# NES_IO_FR.net
KiCad netlist of a schematic drawn in EAGLE
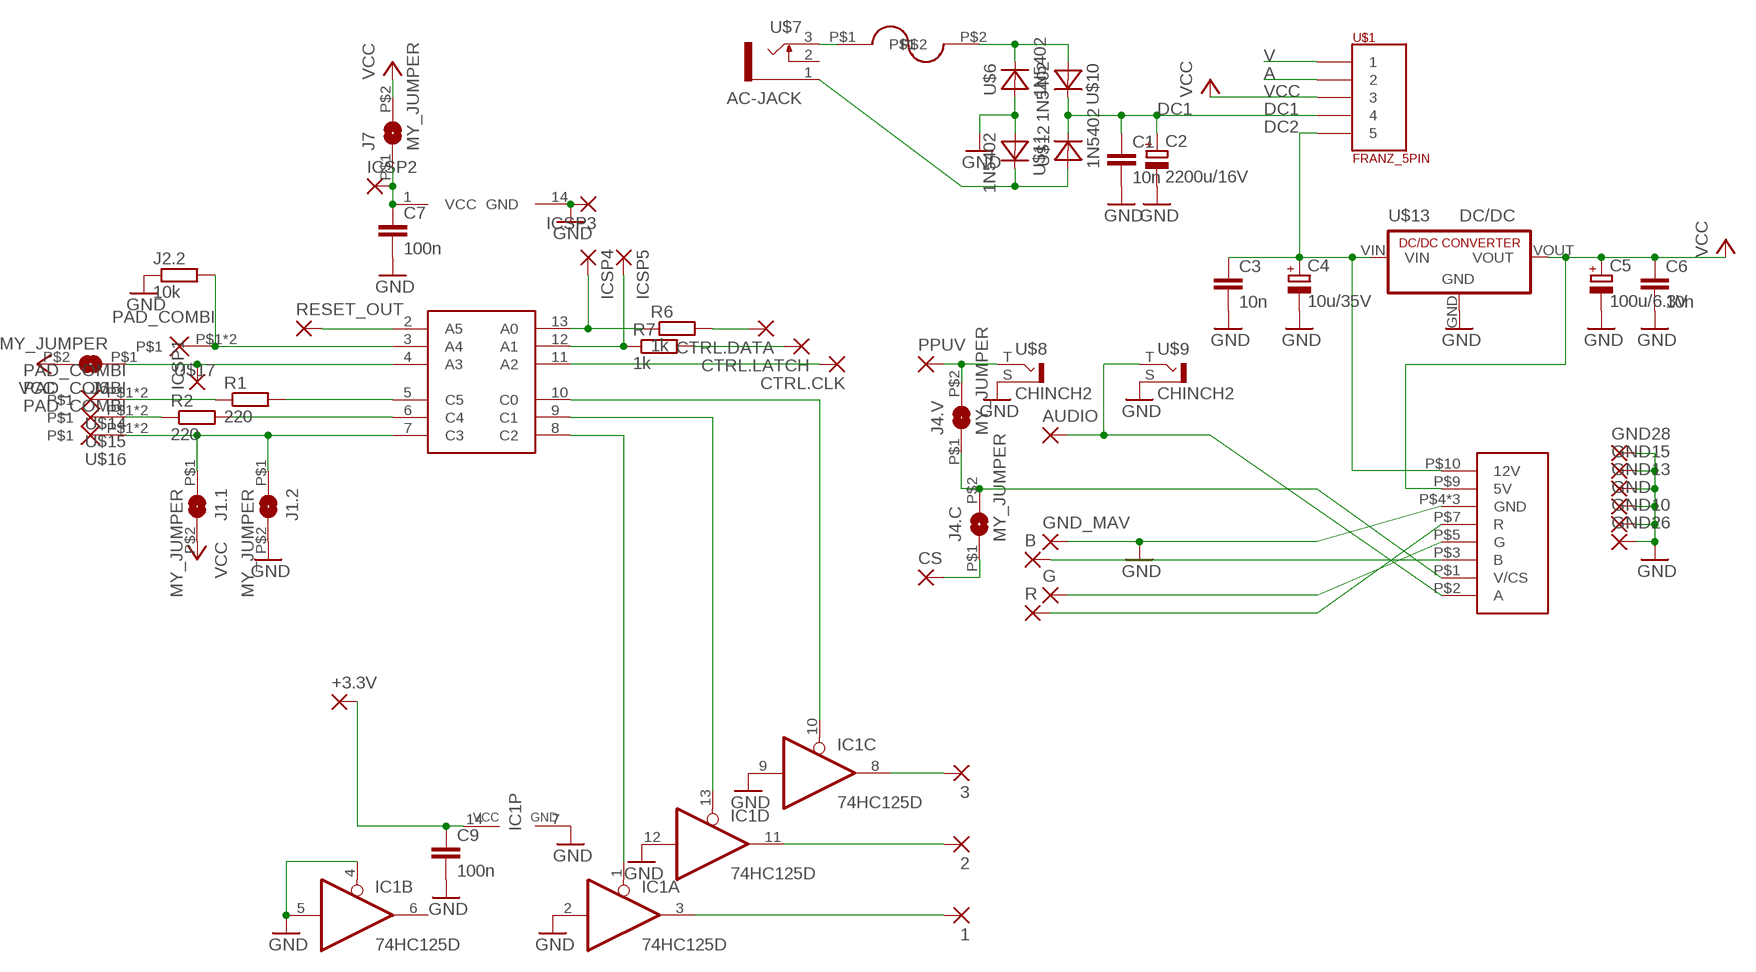
[diagram p0: schematic, sheet 1]

(export (version "E")
  (design (tool "Eeschema 10.0.6"))
  (components
    (comp (ref "+3.3V")
      (value "SMD2")
      (footprint "eagle-import:SMD1,27-2,54")
      (libsource (lib "eagle-import") (part "SMD2"))
    )
    (comp (ref "1")
      (value "SMD2")
      (footprint "eagle-import:SMD1,27-2,54")
      (libsource (lib "eagle-import") (part "SMD2"))
    )
    (comp (ref "2")
      (value "SMD2")
      (footprint "eagle-import:SMD1,27-2,54")
      (libsource (lib "eagle-import") (part "SMD2"))
    )
    (comp (ref "3")
      (value "SMD2")
      (footprint "eagle-import:SMD1,27-2,54")
      (libsource (lib "eagle-import") (part "SMD2"))
    )
    (comp (ref "AUDIO")
      (value "SMD2")
      (footprint "eagle-import:SMD1,27-2,54")
      (libsource (lib "eagle-import") (part "SMD2"))
    )
    (comp (ref "B")
      (value "SMD2")
      (footprint "eagle-import:SMD1,27-2,54")
      (libsource (lib "eagle-import") (part "SMD2"))
    )
    (comp (ref "C1")
      (value "10n")
      (footprint "eagle-import:Z0805")
      (libsource (lib "eagle-import") (part "C0805"))
    )
    (comp (ref "C2")
      (value "2200u/16V")
      (footprint "eagle-import:E5-13")
      (libsource (lib "eagle-import") (part "resistor_CPOL-EUE5-13"))
    )
    (comp (ref "C3")
      (value "10n")
      (footprint "eagle-import:Z0805")
      (libsource (lib "eagle-import") (part "C0805"))
    )
    (comp (ref "C4")
      (value "10u/35V")
      (footprint "eagle-import:PANASONIC_B")
      (libsource (lib "eagle-import") (part "CPOL-EUB"))
    )
    (comp (ref "C5")
      (value "100u/6.3V")
      (footprint "eagle-import:PANASONIC_D")
      (libsource (lib "eagle-import") (part "CPOL-EUD"))
    )
    (comp (ref "C6")
      (value "10n")
      (footprint "eagle-import:Z0805")
      (libsource (lib "eagle-import") (part "C0805"))
    )
    (comp (ref "C7")
      (value "100n")
      (footprint "eagle-import:Z0805")
      (libsource (lib "eagle-import") (part "C0805"))
    )
    (comp (ref "C9")
      (value "100n")
      (footprint "eagle-import:Z0805")
      (libsource (lib "eagle-import") (part "C0805"))
    )
    (comp (ref "CS")
      (value "SMD2")
      (footprint "eagle-import:SMD1,27-2,54")
      (libsource (lib "eagle-import") (part "SMD2"))
    )
    (comp (ref "CTRL.CLK")
      (value "SMD2")
      (footprint "eagle-import:SMD1,27-2,54")
      (libsource (lib "eagle-import") (part "SMD2"))
    )
    (comp (ref "CTRL.DATA")
      (value "SMD2")
      (footprint "eagle-import:SMD1,27-2,54")
      (libsource (lib "eagle-import") (part "SMD2"))
    )
    (comp (ref "CTRL.LATCH")
      (value "SMD2")
      (footprint "eagle-import:SMD1,27-2,54")
      (libsource (lib "eagle-import") (part "SMD2"))
    )
    (comp (ref "G")
      (value "SMD2")
      (footprint "eagle-import:SMD1,27-2,54")
      (libsource (lib "eagle-import") (part "SMD2"))
    )
    (comp (ref "GND")
      (value "SMD5")
      (footprint "eagle-import:SMD2,54-5,08")
      (libsource (lib "eagle-import") (part "SMD5"))
    )
    (comp (ref "GND10")
      (value "SMD5")
      (footprint "eagle-import:SMD2,54-5,08")
      (libsource (lib "eagle-import") (part "SMD5"))
    )
    (comp (ref "GND13")
      (value "SMD5")
      (footprint "eagle-import:SMD2,54-5,08")
      (libsource (lib "eagle-import") (part "SMD5"))
    )
    (comp (ref "GND15")
      (value "SMD5")
      (footprint "eagle-import:SMD2,54-5,08")
      (libsource (lib "eagle-import") (part "SMD5"))
    )
    (comp (ref "GND26")
      (value "SMD5")
      (footprint "eagle-import:SMD2,54-5,08")
      (libsource (lib "eagle-import") (part "SMD5"))
    )
    (comp (ref "GND28")
      (value "SMD5")
      (footprint "eagle-import:SMD2,54-5,08")
      (libsource (lib "eagle-import") (part "SMD5"))
    )
    (comp (ref "GND_MAV")
      (value "SMD2")
      (footprint "eagle-import:SMD1,27-2,54")
      (libsource (lib "eagle-import") (part "SMD2"))
    )
    (comp (ref "IC1")
      (value "74HC125D")
      (footprint "eagle-import:SO14")
      (libsource (lib "eagle-import") (part "74125DHC"))
    )
    (comp (ref "ICSP1")
      (value "1,6/0,8")
      (footprint "eagle-import:1,6_0,8")
      (libsource (lib "eagle-import") (part "1,6/0,8"))
    )
    (comp (ref "ICSP2")
      (value "1,6/0,8")
      (footprint "eagle-import:1,6_0,8")
      (libsource (lib "eagle-import") (part "1,6/0,8"))
    )
    (comp (ref "ICSP3")
      (value "1,6/0,8")
      (footprint "eagle-import:1,6_0,8")
      (libsource (lib "eagle-import") (part "1,6/0,8"))
    )
    (comp (ref "ICSP4")
      (value "1,6/0,8")
      (footprint "eagle-import:1,6_0,8")
      (libsource (lib "eagle-import") (part "1,6/0,8"))
    )
    (comp (ref "ICSP5")
      (value "1,6/0,8")
      (footprint "eagle-import:1,6_0,8")
      (libsource (lib "eagle-import") (part "1,6/0,8"))
    )
    (comp (ref "J1.1")
      (value "MY_JUMPER")
      (footprint "eagle-import:MYJUMP")
      (libsource (lib "eagle-import") (part "MY_JUMPER"))
    )
    (comp (ref "J1.2")
      (value "MY_JUMPER")
      (footprint "eagle-import:MYJUMP")
      (libsource (lib "eagle-import") (part "MY_JUMPER"))
    )
    (comp (ref "J2.2")
      (value "10k")
      (footprint "eagle-import:Z0805")
      (libsource (lib "eagle-import") (part "R0805"))
    )
    (comp (ref "J4.C")
      (value "MY_JUMPER")
      (footprint "eagle-import:MYJUMP")
      (libsource (lib "eagle-import") (part "MY_JUMPER"))
    )
    (comp (ref "J4.V")
      (value "MY_JUMPER")
      (footprint "eagle-import:MYJUMP")
      (libsource (lib "eagle-import") (part "MY_JUMPER"))
    )
    (comp (ref "J6")
      (value "MY_JUMPER")
      (footprint "eagle-import:MYJUMP")
      (libsource (lib "eagle-import") (part "MY_JUMPER"))
    )
    (comp (ref "J7")
      (value "MY_JUMPER")
      (footprint "eagle-import:MYJUMP")
      (libsource (lib "eagle-import") (part "MY_JUMPER"))
    )
    (comp (ref "PPUV")
      (value "SMD2")
      (footprint "eagle-import:SMD1,27-2,54")
      (libsource (lib "eagle-import") (part "SMD2"))
    )
    (comp (ref "R")
      (value "SMD2")
      (footprint "eagle-import:SMD1,27-2,54")
      (libsource (lib "eagle-import") (part "SMD2"))
    )
    (comp (ref "R1")
      (value "220")
      (footprint "eagle-import:Z0805")
      (libsource (lib "eagle-import") (part "R0805"))
    )
    (comp (ref "R2")
      (value "220")
      (footprint "eagle-import:Z0805")
      (libsource (lib "eagle-import") (part "R0805"))
    )
    (comp (ref "R6")
      (value "1k")
      (footprint "eagle-import:Z0805")
      (libsource (lib "eagle-import") (part "R0805"))
    )
    (comp (ref "R7")
      (value "1k")
      (footprint "eagle-import:Z0805")
      (libsource (lib "eagle-import") (part "R0805"))
    )
    (comp (ref "RESET_OUT")
      (value "SMD2")
      (footprint "eagle-import:SMD1,27-2,54")
      (libsource (lib "eagle-import") (part "SMD2"))
    )
    (comp (ref "U$1")
      (value "FRANZ_5PIN")
      (footprint "eagle-import:5X2.22RM4")
      (libsource (lib "eagle-import") (part "FRANZ_5PIN"))
    )
    (comp (ref "U$2")
      (value "FUSEHOLDER")
      (footprint "eagle-import:FUSEHOLDER")
      (libsource (lib "eagle-import") (part "FUSEHOLDER"))
    )
    (comp (ref "U$5")
      (value "PIC16F630_SIMPLE")
      (footprint "eagle-import:PIC16F630")
      (libsource (lib "eagle-import") (part "PIC16F630_SIMPLE"))
    )
    (comp (ref "U$6")
      (value "1N5402")
      (footprint "eagle-import:DO201")
      (libsource (lib "eagle-import") (part "1N5402"))
    )
    (comp (ref "U$7")
      (value "AC-JACK")
      (footprint "eagle-import:AC-JACK")
      (libsource (lib "eagle-import") (part "AC-JACK"))
    )
    (comp (ref "U$8")
      (value "CHINCH2")
      (footprint "eagle-import:CHINCH")
      (libsource (lib "eagle-import") (part "CHINCH2"))
    )
    (comp (ref "U$9")
      (value "CHINCH2")
      (footprint "eagle-import:CHINCH")
      (libsource (lib "eagle-import") (part "CHINCH2"))
    )
    (comp (ref "U$10")
      (value "1N5402")
      (footprint "eagle-import:DO201")
      (libsource (lib "eagle-import") (part "1N5402"))
    )
    (comp (ref "U$11")
      (value "1N5402")
      (footprint "eagle-import:DO201")
      (libsource (lib "eagle-import") (part "1N5402"))
    )
    (comp (ref "U$12")
      (value "1N5402")
      (footprint "eagle-import:DO201")
      (libsource (lib "eagle-import") (part "1N5402"))
    )
    (comp (ref "U$13")
      (value "DC/DC")
      (footprint "eagle-import:RECOM")
      (libsource (lib "eagle-import") (part "DC/DC"))
    )
    (comp (ref "U$14")
      (value "PAD_COMBI")
      (footprint "eagle-import:PAD_COMBI")
      (libsource (lib "eagle-import") (part "PAD_COMBI"))
    )
    (comp (ref "U$15")
      (value "PAD_COMBI")
      (footprint "eagle-import:PAD_COMBI")
      (libsource (lib "eagle-import") (part "PAD_COMBI"))
    )
    (comp (ref "U$16")
      (value "PAD_COMBI")
      (footprint "eagle-import:PAD_COMBI")
      (libsource (lib "eagle-import") (part "PAD_COMBI"))
    )
    (comp (ref "U$17")
      (value "PAD_COMBI")
      (footprint "eagle-import:PAD_COMBI")
      (libsource (lib "eagle-import") (part "PAD_COMBI"))
    )
    (comp (ref "U$18")
      (value "NESFR_JACK")
      (footprint "eagle-import:NESFR_JACK")
      (libsource (lib "eagle-import") (part "NESFR_JACK"))
    )
  )
  (nets
    (net (code "1") (name "/A") (class "Default")
      (node (ref "U$1") (pin "P$2") (pinfunction "2_P$2") (pintype "bidirectional"))
    )
    (net (code "2") (name "/DC1") (class "Default")
      (node (ref "C1") (pin "1") (pinfunction "1_1") (pintype "passive"))
      (node (ref "C2") (pin "+") (pinfunction "+_+") (pintype "passive"))
      (node (ref "U$1") (pin "P$4") (pinfunction "4_P$4") (pintype "bidirectional"))
      (node (ref "U$10") (pin "C") (pinfunction "C_C") (pintype "passive"))
      (node (ref "U$12") (pin "C") (pinfunction "C_C") (pintype "passive"))
    )
    (net (code "3") (name "/DC2") (class "Default")
      (node (ref "C3") (pin "1") (pinfunction "1_1") (pintype "passive"))
      (node (ref "C4") (pin "+") (pinfunction "+_+") (pintype "passive"))
      (node (ref "U$1") (pin "P$5") (pinfunction "5_P$5") (pintype "bidirectional"))
      (node (ref "U$13") (pin "VIN") (pinfunction "VIN_VIN") (pintype "passive"))
      (node (ref "U$18") (pin "P$10") (pinfunction "12V_P$10") (pintype "bidirectional"))
    )
    (net (code "4") (name "/V") (class "Default")
      (node (ref "U$1") (pin "P$1") (pinfunction "1_P$1") (pintype "bidirectional"))
    )
    (net (code "5") (name "GND") (class "Default")
      (node (ref "C1") (pin "2") (pinfunction "2_2") (pintype "passive"))
      (node (ref "C2") (pin "-") (pinfunction "-_-") (pintype "passive"))
      (node (ref "C3") (pin "2") (pinfunction "2_2") (pintype "passive"))
      (node (ref "C4") (pin "-") (pinfunction "-_-") (pintype "passive"))
      (node (ref "C5") (pin "-") (pinfunction "-_-") (pintype "passive"))
      (node (ref "C6") (pin "2") (pinfunction "2_2") (pintype "passive"))
      (node (ref "C7") (pin "2") (pinfunction "2_2") (pintype "passive"))
      (node (ref "C9") (pin "2") (pinfunction "2_2") (pintype "passive"))
      (node (ref "GND") (pin "1") (pinfunction "P_1") (pintype "passive"))
      (node (ref "GND10") (pin "1") (pinfunction "P_1") (pintype "passive"))
      (node (ref "GND13") (pin "1") (pinfunction "P_1") (pintype "passive"))
      (node (ref "GND15") (pin "1") (pinfunction "P_1") (pintype "passive"))
      (node (ref "GND26") (pin "1") (pinfunction "P_1") (pintype "passive"))
      (node (ref "GND28") (pin "1") (pinfunction "P_1") (pintype "passive"))
      (node (ref "GND_MAV") (pin "1") (pinfunction "P_1") (pintype "passive"))
      (node (ref "IC1") (pin "12") (pinfunction "I_12") (pintype "input"))
      (node (ref "IC1") (pin "2") (pinfunction "I_2") (pintype "input"))
      (node (ref "IC1") (pin "4") (pinfunction "OE_4") (pintype "input"))
      (node (ref "IC1") (pin "5") (pinfunction "I_5") (pintype "input"))
      (node (ref "IC1") (pin "7") (pinfunction "GND_7") (pintype "power_in"))
      (node (ref "IC1") (pin "9") (pinfunction "I_9") (pintype "input"))
      (node (ref "ICSP3") (pin "1") (pinfunction "P_1") (pintype "passive"))
      (node (ref "J1.2") (pin "P$2") (pinfunction "2_P$2") (pintype "passive"))
      (node (ref "J2.2") (pin "1") (pinfunction "1_1") (pintype "passive"))
      (node (ref "U$11") (pin "A") (pinfunction "A_A") (pintype "passive"))
      (node (ref "U$13") (pin "GND") (pinfunction "GND_GND") (pintype "passive"))
      (node (ref "U$18") (pin "P$4") (pinfunction "GND_P$4") (pintype "bidirectional"))
      (node (ref "U$18") (pin "P$6") (pinfunction "GND_P$6") (pintype "bidirectional"))
      (node (ref "U$18") (pin "P$8") (pinfunction "GND_P$8") (pintype "bidirectional"))
      (node (ref "U$5") (pin "14") (pinfunction "GND_14") (pintype "bidirectional"))
      (node (ref "U$6") (pin "A") (pinfunction "A_A") (pintype "passive"))
      (node (ref "U$8") (pin "S") (pinfunction "S_S") (pintype "passive"))
      (node (ref "U$9") (pin "S") (pinfunction "S_S") (pintype "passive"))
    )
    (net (code "6") (name "Net-(+3.3V-P)") (class "Default")
      (node (ref "+3.3V") (pin "1") (pinfunction "P_1") (pintype "passive"))
      (node (ref "C9") (pin "1") (pinfunction "1_1") (pintype "passive"))
      (node (ref "IC1") (pin "14") (pinfunction "VCC_14") (pintype "power_in"))
    )
    (net (code "7") (name "Net-(1-P)") (class "Default")
      (node (ref "1") (pin "1") (pinfunction "P_1") (pintype "passive"))
      (node (ref "IC1") (pin "3") (pinfunction "O_3") (pintype "tri_state"))
    )
    (net (code "8") (name "Net-(2-P)") (class "Default")
      (node (ref "2") (pin "1") (pinfunction "P_1") (pintype "passive"))
      (node (ref "IC1") (pin "11") (pinfunction "O_11") (pintype "tri_state"))
    )
    (net (code "9") (name "Net-(3-P)") (class "Default")
      (node (ref "3") (pin "1") (pinfunction "P_1") (pintype "passive"))
      (node (ref "IC1") (pin "8") (pinfunction "O_8") (pintype "tri_state"))
    )
    (net (code "10") (name "Net-(AUDIO-P)") (class "Default")
      (node (ref "AUDIO") (pin "1") (pinfunction "P_1") (pintype "passive"))
      (node (ref "U$18") (pin "P$2") (pinfunction "A_P$2") (pintype "bidirectional"))
      (node (ref "U$9") (pin "T") (pinfunction "T_T") (pintype "passive"))
    )
    (net (code "11") (name "Net-(B-P)") (class "Default")
      (node (ref "B") (pin "1") (pinfunction "P_1") (pintype "passive"))
      (node (ref "U$18") (pin "P$3") (pinfunction "B_P$3") (pintype "bidirectional"))
    )
    (net (code "12") (name "Net-(CS-P)") (class "Default")
      (node (ref "CS") (pin "1") (pinfunction "P_1") (pintype "passive"))
      (node (ref "J4.C") (pin "P$1") (pinfunction "1_P$1") (pintype "passive"))
    )
    (net (code "13") (name "Net-(CTRL.CLK-P)") (class "Default")
      (node (ref "CTRL.CLK") (pin "1") (pinfunction "P_1") (pintype "passive"))
      (node (ref "U$5") (pin "11") (pinfunction "A2_11") (pintype "bidirectional"))
    )
    (net (code "14") (name "Net-(CTRL.DATA-P)") (class "Default")
      (node (ref "CTRL.DATA") (pin "1") (pinfunction "P_1") (pintype "passive"))
      (node (ref "R6") (pin "2") (pinfunction "2_2") (pintype "passive"))
    )
    (net (code "15") (name "Net-(CTRL.LATCH-P)") (class "Default")
      (node (ref "CTRL.LATCH") (pin "1") (pinfunction "P_1") (pintype "passive"))
      (node (ref "R7") (pin "2") (pinfunction "2_2") (pintype "passive"))
    )
    (net (code "16") (name "Net-(G-P)") (class "Default")
      (node (ref "G") (pin "1") (pinfunction "P_1") (pintype "passive"))
      (node (ref "U$18") (pin "P$5") (pinfunction "G_P$5") (pintype "bidirectional"))
    )
    (net (code "17") (name "Net-(IC1A-OE)") (class "Default")
      (node (ref "IC1") (pin "1") (pinfunction "OE_1") (pintype "input"))
      (node (ref "U$5") (pin "8") (pinfunction "C2_8") (pintype "bidirectional"))
    )
    (net (code "18") (name "Net-(IC1C-OE)") (class "Default")
      (node (ref "IC1") (pin "10") (pinfunction "OE_10") (pintype "input"))
      (node (ref "U$5") (pin "10") (pinfunction "C0_10") (pintype "bidirectional"))
    )
    (net (code "19") (name "Net-(IC1D-OE)") (class "Default")
      (node (ref "IC1") (pin "13") (pinfunction "OE_13") (pintype "input"))
      (node (ref "U$5") (pin "9") (pinfunction "C1_9") (pintype "bidirectional"))
    )
    (net (code "20") (name "Net-(ICSP1-P)") (class "Default")
      (node (ref "ICSP1") (pin "1") (pinfunction "P_1") (pintype "passive"))
      (node (ref "J6") (pin "P$1") (pinfunction "1_P$1") (pintype "passive"))
      (node (ref "U$5") (pin "4") (pinfunction "A3_4") (pintype "bidirectional"))
    )
    (net (code "21") (name "Net-(ICSP2-P)") (class "Default")
      (node (ref "C7") (pin "1") (pinfunction "1_1") (pintype "passive"))
      (node (ref "ICSP2") (pin "1") (pinfunction "P_1") (pintype "passive"))
      (node (ref "J7") (pin "P$1") (pinfunction "1_P$1") (pintype "passive"))
      (node (ref "U$5") (pin "1") (pinfunction "VCC_1") (pintype "bidirectional"))
    )
    (net (code "22") (name "Net-(ICSP4-P)") (class "Default")
      (node (ref "ICSP4") (pin "1") (pinfunction "P_1") (pintype "passive"))
      (node (ref "R6") (pin "1") (pinfunction "1_1") (pintype "passive"))
      (node (ref "U$5") (pin "13") (pinfunction "A0_13") (pintype "bidirectional"))
    )
    (net (code "23") (name "Net-(ICSP5-P)") (class "Default")
      (node (ref "ICSP5") (pin "1") (pinfunction "P_1") (pintype "passive"))
      (node (ref "R7") (pin "1") (pinfunction "1_1") (pintype "passive"))
      (node (ref "U$5") (pin "12") (pinfunction "A1_12") (pintype "bidirectional"))
    )
    (net (code "24") (name "Net-(J1.1-1)") (class "Default")
      (node (ref "J1.1") (pin "P$1") (pinfunction "1_P$1") (pintype "passive"))
      (node (ref "J1.2") (pin "P$1") (pinfunction "1_P$1") (pintype "passive"))
      (node (ref "U$16") (pin "P$1") (pinfunction "P$1_P$1") (pintype "bidirectional"))
      (node (ref "U$16") (pin "P$2") (pinfunction "P$1_P$2") (pintype "bidirectional"))
      (node (ref "U$5") (pin "7") (pinfunction "C3_7") (pintype "bidirectional"))
    )
    (net (code "25") (name "Net-(J4.C-2)") (class "Default")
      (node (ref "J4.C") (pin "P$2") (pinfunction "2_P$2") (pintype "passive"))
      (node (ref "J4.V") (pin "P$1") (pinfunction "1_P$1") (pintype "passive"))
      (node (ref "U$18") (pin "P$1") (pinfunction "V/CS_P$1") (pintype "bidirectional"))
    )
    (net (code "26") (name "Net-(J4.V-2)") (class "Default")
      (node (ref "J4.V") (pin "P$2") (pinfunction "2_P$2") (pintype "passive"))
      (node (ref "PPUV") (pin "1") (pinfunction "P_1") (pintype "passive"))
      (node (ref "U$8") (pin "T") (pinfunction "T_T") (pintype "passive"))
    )
    (net (code "27") (name "Net-(R-P)") (class "Default")
      (node (ref "R") (pin "1") (pinfunction "P_1") (pintype "passive"))
      (node (ref "U$18") (pin "P$7") (pinfunction "R_P$7") (pintype "bidirectional"))
    )
    (net (code "28") (name "Net-(R1-Pad1)") (class "Default")
      (node (ref "R1") (pin "1") (pinfunction "1_1") (pintype "passive"))
      (node (ref "U$14") (pin "P$1") (pinfunction "P$1_P$1") (pintype "bidirectional"))
      (node (ref "U$14") (pin "P$2") (pinfunction "P$1_P$2") (pintype "bidirectional"))
    )
    (net (code "29") (name "Net-(R2-Pad1)") (class "Default")
      (node (ref "R2") (pin "1") (pinfunction "1_1") (pintype "passive"))
      (node (ref "U$15") (pin "P$1") (pinfunction "P$1_P$1") (pintype "bidirectional"))
      (node (ref "U$15") (pin "P$2") (pinfunction "P$1_P$2") (pintype "bidirectional"))
    )
    (net (code "30") (name "Net-(RESET_OUT-P)") (class "Default")
      (node (ref "RESET_OUT") (pin "1") (pinfunction "P_1") (pintype "passive"))
      (node (ref "U$5") (pin "2") (pinfunction "A5_2") (pintype "bidirectional"))
    )
    (net (code "31") (name "Net-(U$2-PadP$1)") (class "Default")
      (node (ref "U$2") (pin "P$1") (pinfunction "P$1_P$1") (pintype "bidirectional"))
      (node (ref "U$7") (pin "3") (pinfunction "3_3") (pintype "passive"))
    )
    (net (code "32") (name "Net-(U$5A-A4)") (class "Default")
      (node (ref "J2.2") (pin "2") (pinfunction "2_2") (pintype "passive"))
      (node (ref "U$17") (pin "P$1") (pinfunction "P$1_P$1") (pintype "bidirectional"))
      (node (ref "U$17") (pin "P$2") (pinfunction "P$1_P$2") (pintype "bidirectional"))
      (node (ref "U$5") (pin "3") (pinfunction "A4_3") (pintype "bidirectional"))
    )
    (net (code "33") (name "Net-(U$5A-C4)") (class "Default")
      (node (ref "R2") (pin "2") (pinfunction "2_2") (pintype "passive"))
      (node (ref "U$5") (pin "6") (pinfunction "C4_6") (pintype "bidirectional"))
    )
    (net (code "34") (name "Net-(U$5A-C5)") (class "Default")
      (node (ref "R1") (pin "2") (pinfunction "2_2") (pintype "passive"))
      (node (ref "U$5") (pin "5") (pinfunction "C5_5") (pintype "bidirectional"))
    )
    (net (code "35") (name "Net-(U$7-5)") (class "Default")
      (node (ref "U$11") (pin "C") (pinfunction "C_C") (pintype "passive"))
      (node (ref "U$12") (pin "A") (pinfunction "A_A") (pintype "passive"))
      (node (ref "U$7") (pin "1") (pinfunction "5_1") (pintype "passive"))
    )
    (net (code "36") (name "Net-(U$10-PadA)") (class "Default")
      (node (ref "U$10") (pin "A") (pinfunction "A_A") (pintype "passive"))
      (node (ref "U$2") (pin "P$2") (pinfunction "P$2_P$2") (pintype "bidirectional"))
      (node (ref "U$6") (pin "C") (pinfunction "C_C") (pintype "passive"))
    )
    (net (code "37") (name "VCC") (class "Default")
      (node (ref "C5") (pin "+") (pinfunction "+_+") (pintype "passive"))
      (node (ref "C6") (pin "1") (pinfunction "1_1") (pintype "passive"))
      (node (ref "J1.1") (pin "P$2") (pinfunction "2_P$2") (pintype "passive"))
      (node (ref "J6") (pin "P$2") (pinfunction "2_P$2") (pintype "passive"))
      (node (ref "J7") (pin "P$2") (pinfunction "2_P$2") (pintype "passive"))
      (node (ref "U$1") (pin "P$3") (pinfunction "3_P$3") (pintype "bidirectional"))
      (node (ref "U$13") (pin "VOUT") (pinfunction "VOUT_VOUT") (pintype "passive"))
      (node (ref "U$18") (pin "P$9") (pinfunction "5V_P$9") (pintype "bidirectional"))
    )
    (net (code "38") (name "unconnected-(IC1B-O-Pad6)") (class "Default")
      (node (ref "IC1") (pin "6") (pinfunction "O_6") (pintype "tri_state"))
    )
    (net (code "39") (name "unconnected-(U$7-4-Pad2)") (class "Default")
      (node (ref "U$7") (pin "2") (pinfunction "4_2") (pintype "passive"))
    )
  )
)
